# ET-FLASHEEPROM.net
KiCad netlist of a schematic drawn in Altium Designer
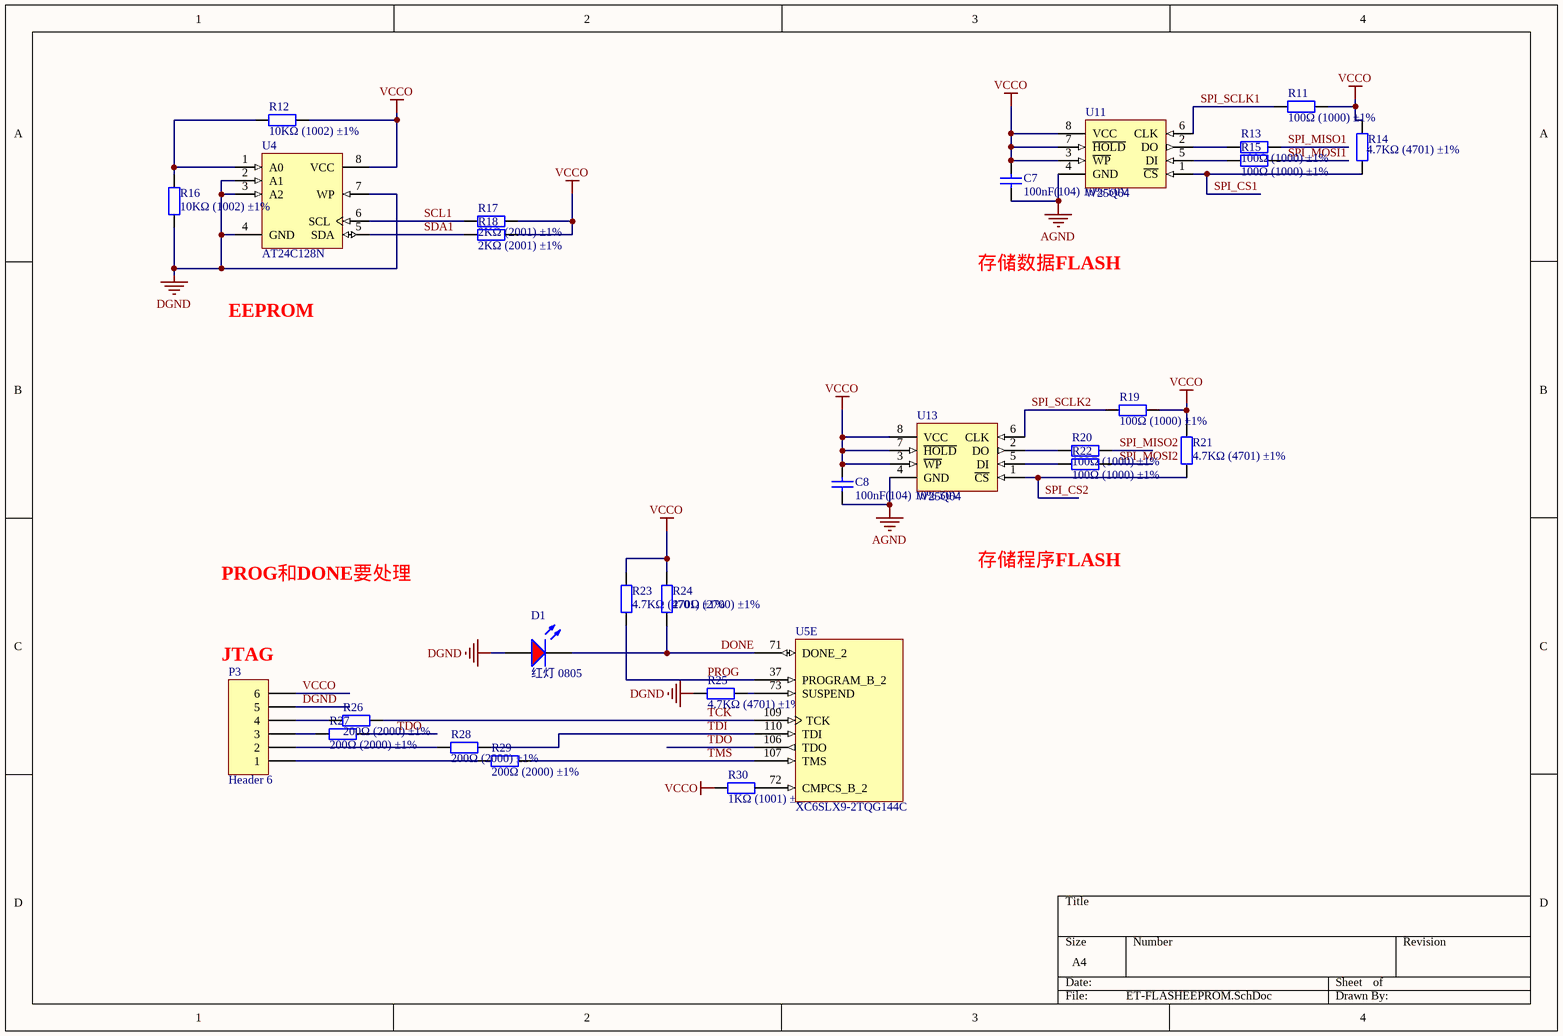
[diagram p0: ET-FLASHEEPROM.SchDoc]

(export (version "E")
  (design (tool "Eeschema 10.0.6"))
  (components
    (comp (ref "C7")
      (value "100nF(104) 10% 50V")
      (footprint "LC-0805_C")
      (description "贴片电容")
      (libsource (lib "Miscellaneous Devices LC") (part "0805 100nF(104) 10% 50V"))
    )
    (comp (ref "C8")
      (value "100nF(104) 10% 50V")
      (footprint "LC-0805_C")
      (description "贴片电容")
      (libsource (lib "Miscellaneous Devices LC") (part "0805 100nF(104) 10% 50V"))
    )
    (comp (ref "D1")
      (value "红灯 0805")
      (footprint "LC-0805_LED_S1")
      (description "发光二极管")
      (libsource (lib "Miscellaneous Devices LC") (part "0805 红灯"))
    )
    (comp (ref "P3")
      (value "Header 6")
      (footprint "HDR1X6")
      (description "Header, 6-Pin")
      (fields (field (name "PUBLISHER") "Altium Limited"))
      (libsource (lib "Miscellaneous Connectors") (part "Header 6"))
    )
    (comp (ref "R11")
      (value "100Ω (1000) ±1%")
      (footprint "LC-0805_R")
      (description "贴片电阻")
      (libsource (lib "Miscellaneous Devices LC") (part "0805 100Ω (1000) 1%"))
    )
    (comp (ref "R12")
      (value "10KΩ (1002) ±1%")
      (footprint "LC-0805_R")
      (description "贴片电阻")
      (libsource (lib "") (part "0805 10KΩ (1002) 1%_1"))
    )
    (comp (ref "R13")
      (value "100Ω (1000) ±1%")
      (footprint "LC-0805_R")
      (description "贴片电阻")
      (libsource (lib "Miscellaneous Devices LC") (part "0805 100Ω (1000) 1%"))
    )
    (comp (ref "R14")
      (value "4.7KΩ (4701) ±1%")
      (footprint "LC-0805_R")
      (description "贴片电阻")
      (libsource (lib "Miscellaneous Devices LC") (part "0805 4.7KΩ (4701) 1%"))
    )
    (comp (ref "R15")
      (value "100Ω (1000) ±1%")
      (footprint "LC-0805_R")
      (description "贴片电阻")
      (libsource (lib "Miscellaneous Devices LC") (part "0805 100Ω (1000) 1%"))
    )
    (comp (ref "R16")
      (value "10KΩ (1002) ±1%")
      (footprint "LC-0805_R")
      (description "贴片电阻")
      (libsource (lib "Miscellaneous Devices LC") (part "0805 10KΩ (1002) 1%"))
    )
    (comp (ref "R17")
      (value "2KΩ (2001) ±1%")
      (footprint "LC-0805_R")
      (description "贴片电阻")
      (libsource (lib "Miscellaneous Devices LC") (part "0805 2KΩ (2001) 1%"))
    )
    (comp (ref "R18")
      (value "2KΩ (2001) ±1%")
      (footprint "LC-0805_R")
      (description "贴片电阻")
      (libsource (lib "Miscellaneous Devices LC") (part "0805 2KΩ (2001) 1%"))
    )
    (comp (ref "R19")
      (value "100Ω (1000) ±1%")
      (footprint "LC-0805_R")
      (description "贴片电阻")
      (libsource (lib "Miscellaneous Devices LC") (part "0805 100Ω (1000) 1%"))
    )
    (comp (ref "R20")
      (value "100Ω (1000) ±1%")
      (footprint "LC-0805_R")
      (description "贴片电阻")
      (libsource (lib "Miscellaneous Devices LC") (part "0805 100Ω (1000) 1%"))
    )
    (comp (ref "R21")
      (value "4.7KΩ (4701) ±1%")
      (footprint "LC-0805_R")
      (description "贴片电阻")
      (libsource (lib "Miscellaneous Devices LC") (part "0805 4.7KΩ (4701) 1%"))
    )
    (comp (ref "R22")
      (value "100Ω (1000) ±1%")
      (footprint "LC-0805_R")
      (description "贴片电阻")
      (libsource (lib "Miscellaneous Devices LC") (part "0805 100Ω (1000) 1%"))
    )
    (comp (ref "R23")
      (value "4.7KΩ (4701) ±1%")
      (footprint "LC-0805_R")
      (description "贴片电阻")
      (libsource (lib "Miscellaneous Devices LC") (part "0805 4.7KΩ (4701) 1%"))
    )
    (comp (ref "R24")
      (value "270Ω (2700) ±1%")
      (footprint "LC-0805_R")
      (description "贴片电阻")
      (libsource (lib "Miscellaneous Devices LC") (part "0805 270Ω (2700) 1%"))
    )
    (comp (ref "R25")
      (value "4.7KΩ (4701) ±1%")
      (footprint "LC-0805_R")
      (description "贴片电阻")
      (libsource (lib "") (part "0805 4.7KΩ (4701) 1%_1"))
    )
    (comp (ref "R26")
      (value "200Ω (2000) ±1%")
      (footprint "LC-0805_R")
      (description "贴片电阻")
      (libsource (lib "Miscellaneous Devices LC") (part "0805 200Ω (2000) 1%"))
    )
    (comp (ref "R27")
      (value "200Ω (2000) ±1%")
      (footprint "LC-0805_R")
      (description "贴片电阻")
      (libsource (lib "Miscellaneous Devices LC") (part "0805 200Ω (2000) 1%"))
    )
    (comp (ref "R28")
      (value "200Ω (2000) ±1%")
      (footprint "LC-0805_R")
      (description "贴片电阻")
      (libsource (lib "Miscellaneous Devices LC") (part "0805 200Ω (2000) 1%"))
    )
    (comp (ref "R29")
      (value "200Ω (2000) ±1%")
      (footprint "LC-0805_R")
      (description "贴片电阻")
      (libsource (lib "Miscellaneous Devices LC") (part "0805 200Ω (2000) 1%"))
    )
    (comp (ref "R30")
      (value "1KΩ (1001) ±1%")
      (footprint "LC-0805_R")
      (description "贴片电阻")
      (libsource (lib "Miscellaneous Devices LC") (part "0805 1KΩ (1001) 1%"))
    )
    (comp (ref "U4")
      (value "AT24C128N")
      (footprint "8P3")
      (description "1Kbit (128 x 8), 2-wire Bus Automotive Serial EEPROM with Write Protect, 2.5V, 8-Pin SOIC, Bulk")
      (fields (field (name "PUBLISHER") "Altium Limited"))
      (libsource (lib "Atmel Memory Serial EEPROM") (part "AT24C01BN-SP25-B"))
    )
    (comp (ref "U5")
      (value "XC6SLX9-2TQG144C")
      (footprint "TQG144_N")
      (fields (field (name "PUBLISHER") "Altium Limited"))
      (libsource (lib "Xilinx Spartan-6") (part "XC6SLX9-2TQG144C"))
    )
    (comp (ref "U11")
      (value "W25Q64")
      (footprint "LC-SOIC-8_208mil")
      (libsource (lib "My Library") (part "W25Q64"))
    )
    (comp (ref "U13")
      (value "W25Q64")
      (footprint "LC-SOIC-8_208mil")
      (libsource (lib "My Library") (part "W25Q64"))
    )
  )
  (nets
    (net (code "1") (name "/DONE") (class "Default")
      (node (ref "D1") (pin "K") (pinfunction "K_K") (pintype "passive"))
      (node (ref "R24") (pin "1") (pinfunction "1_1") (pintype "passive"))
      (node (ref "U5") (pin "71") (pinfunction "DONE_2_71") (pintype "bidirectional"))
    )
    (net (code "2") (name "/PROG") (class "Default")
      (node (ref "R23") (pin "1") (pinfunction "1_1") (pintype "passive"))
      (node (ref "U5") (pin "37") (pinfunction "PROGRAM_B_2_37") (pintype "input"))
    )
    (net (code "3") (name "/SCL1") (class "Default")
      (node (ref "R17") (pin "1") (pinfunction "1_1") (pintype "passive"))
      (node (ref "U4") (pin "6") (pinfunction "SCL_6") (pintype "input"))
    )
    (net (code "4") (name "/SDA1") (class "Default")
      (node (ref "R18") (pin "1") (pinfunction "1_1") (pintype "passive"))
      (node (ref "U4") (pin "5") (pinfunction "SDA_5") (pintype "bidirectional"))
    )
    (net (code "5") (name "/SPI_CS1") (class "Default")
      (node (ref "R14") (pin "1") (pinfunction "1_1") (pintype "passive"))
      (node (ref "U11") (pin "1") (pinfunction "~{CS}_1") (pintype "input"))
    )
    (net (code "6") (name "/SPI_CS2") (class "Default")
      (node (ref "R21") (pin "1") (pinfunction "1_1") (pintype "passive"))
      (node (ref "U13") (pin "1") (pinfunction "~{CS}_1") (pintype "input"))
    )
    (net (code "7") (name "/SPI_MISO1") (class "Default")
      (node (ref "R13") (pin "2") (pinfunction "2_2") (pintype "passive"))
    )
    (net (code "8") (name "/SPI_MISO2") (class "Default")
      (node (ref "R20") (pin "2") (pinfunction "2_2") (pintype "passive"))
    )
    (net (code "9") (name "/SPI_MOSI1") (class "Default")
      (node (ref "R15") (pin "2") (pinfunction "2_2") (pintype "passive"))
    )
    (net (code "10") (name "/SPI_MOSI2") (class "Default")
      (node (ref "R22") (pin "2") (pinfunction "2_2") (pintype "passive"))
    )
    (net (code "11") (name "/SPI_SCLK1") (class "Default")
      (node (ref "R11") (pin "1") (pinfunction "1_1") (pintype "passive"))
      (node (ref "U11") (pin "6") (pinfunction "CLK_6") (pintype "input"))
    )
    (net (code "12") (name "/SPI_SCLK2") (class "Default")
      (node (ref "R19") (pin "1") (pinfunction "1_1") (pintype "passive"))
      (node (ref "U13") (pin "6") (pinfunction "CLK_6") (pintype "input"))
    )
    (net (code "13") (name "/TCK") (class "Default")
      (node (ref "R26") (pin "2") (pinfunction "2_2") (pintype "passive"))
      (node (ref "U5") (pin "109") (pinfunction "TCK_109") (pintype "input"))
    )
    (net (code "14") (name "/TDI") (class "Default")
      (node (ref "R28") (pin "2") (pinfunction "2_2") (pintype "passive"))
      (node (ref "U5") (pin "110") (pinfunction "TDI_110") (pintype "input"))
    )
    (net (code "15") (name "/TDO") (class "Default")
      (node (ref "R27") (pin "2") (pinfunction "2_2") (pintype "passive"))
      (node (ref "U5") (pin "106") (pinfunction "TDO_106") (pintype "output"))
    )
    (net (code "16") (name "/TMS") (class "Default")
      (node (ref "R29") (pin "2") (pinfunction "2_2") (pintype "passive"))
      (node (ref "U5") (pin "107") (pinfunction "TMS_107") (pintype "input"))
    )
    (net (code "17") (name "AGND") (class "Default")
      (node (ref "C7") (pin "1") (pinfunction "1_1") (pintype "passive"))
      (node (ref "C8") (pin "1") (pinfunction "1_1") (pintype "passive"))
      (node (ref "U11") (pin "4") (pinfunction "GND_4") (pintype "power_in"))
      (node (ref "U13") (pin "4") (pinfunction "GND_4") (pintype "power_in"))
    )
    (net (code "18") (name "DGND") (class "Default")
      (node (ref "D1") (pin "A") (pinfunction "A_A") (pintype "passive"))
      (node (ref "P3") (pin "5") (pinfunction "5_5") (pintype "passive"))
      (node (ref "R16") (pin "1") (pinfunction "1_1") (pintype "passive"))
      (node (ref "R25") (pin "1") (pinfunction "1_1") (pintype "passive"))
      (node (ref "U4") (pin "2") (pinfunction "A1_2") (pintype "input"))
      (node (ref "U4") (pin "3") (pinfunction "A2_3") (pintype "input"))
      (node (ref "U4") (pin "4") (pinfunction "GND_4") (pintype "power_in"))
      (node (ref "U4") (pin "7") (pinfunction "WP_7") (pintype "input"))
    )
    (net (code "19") (name "Net-(P3-Pad1)") (class "Default")
      (node (ref "P3") (pin "1") (pinfunction "1_1") (pintype "passive"))
      (node (ref "R29") (pin "1") (pinfunction "1_1") (pintype "passive"))
    )
    (net (code "20") (name "Net-(P3-Pad2)") (class "Default")
      (node (ref "P3") (pin "2") (pinfunction "2_2") (pintype "passive"))
      (node (ref "R28") (pin "1") (pinfunction "1_1") (pintype "passive"))
    )
    (net (code "21") (name "Net-(P3-Pad3)") (class "Default")
      (node (ref "P3") (pin "3") (pinfunction "3_3") (pintype "passive"))
      (node (ref "R27") (pin "1") (pinfunction "1_1") (pintype "passive"))
    )
    (net (code "22") (name "Net-(P3-Pad4)") (class "Default")
      (node (ref "P3") (pin "4") (pinfunction "4_4") (pintype "passive"))
      (node (ref "R26") (pin "1") (pinfunction "1_1") (pintype "passive"))
    )
    (net (code "23") (name "Net-(U4-A0)") (class "Default")
      (node (ref "R12") (pin "1") (pinfunction "1_1") (pintype "passive"))
      (node (ref "R16") (pin "2") (pinfunction "2_2") (pintype "passive"))
      (node (ref "U4") (pin "1") (pinfunction "A0_1") (pintype "input"))
    )
    (net (code "24") (name "Net-(U5E-CMPCS_B_2)") (class "Default")
      (node (ref "R30") (pin "2") (pinfunction "2_2") (pintype "passive"))
      (node (ref "U5") (pin "72") (pinfunction "CMPCS_B_2_72") (pintype "input"))
    )
    (net (code "25") (name "Net-(U5E-SUSPEND)") (class "Default")
      (node (ref "R25") (pin "2") (pinfunction "2_2") (pintype "passive"))
      (node (ref "U5") (pin "73") (pinfunction "SUSPEND_73") (pintype "input"))
    )
    (net (code "26") (name "Net-(U11-DI)") (class "Default")
      (node (ref "R15") (pin "1") (pinfunction "1_1") (pintype "passive"))
      (node (ref "U11") (pin "5") (pinfunction "DI_5") (pintype "input"))
    )
    (net (code "27") (name "Net-(U11-DO)") (class "Default")
      (node (ref "R13") (pin "1") (pinfunction "1_1") (pintype "passive"))
      (node (ref "U11") (pin "2") (pinfunction "DO_2") (pintype "output"))
    )
    (net (code "28") (name "Net-(U13-DI)") (class "Default")
      (node (ref "R22") (pin "1") (pinfunction "1_1") (pintype "passive"))
      (node (ref "U13") (pin "5") (pinfunction "DI_5") (pintype "input"))
    )
    (net (code "29") (name "Net-(U13-DO)") (class "Default")
      (node (ref "R20") (pin "1") (pinfunction "1_1") (pintype "passive"))
      (node (ref "U13") (pin "2") (pinfunction "DO_2") (pintype "output"))
    )
    (net (code "30") (name "VCCO") (class "Default")
      (node (ref "C7") (pin "2") (pinfunction "2_2") (pintype "passive"))
      (node (ref "C8") (pin "2") (pinfunction "2_2") (pintype "passive"))
      (node (ref "P3") (pin "6") (pinfunction "6_6") (pintype "passive"))
      (node (ref "R11") (pin "2") (pinfunction "2_2") (pintype "passive"))
      (node (ref "R12") (pin "2") (pinfunction "2_2") (pintype "passive"))
      (node (ref "R14") (pin "2") (pinfunction "2_2") (pintype "passive"))
      (node (ref "R17") (pin "2") (pinfunction "2_2") (pintype "passive"))
      (node (ref "R18") (pin "2") (pinfunction "2_2") (pintype "passive"))
      (node (ref "R19") (pin "2") (pinfunction "2_2") (pintype "passive"))
      (node (ref "R21") (pin "2") (pinfunction "2_2") (pintype "passive"))
      (node (ref "R23") (pin "2") (pinfunction "2_2") (pintype "passive"))
      (node (ref "R24") (pin "2") (pinfunction "2_2") (pintype "passive"))
      (node (ref "R30") (pin "1") (pinfunction "1_1") (pintype "passive"))
      (node (ref "U11") (pin "3") (pinfunction "~{WP}_3") (pintype "input"))
      (node (ref "U11") (pin "7") (pinfunction "~{HOLD}_7") (pintype "input"))
      (node (ref "U11") (pin "8") (pinfunction "VCC_8") (pintype "power_in"))
      (node (ref "U13") (pin "3") (pinfunction "~{WP}_3") (pintype "input"))
      (node (ref "U13") (pin "7") (pinfunction "~{HOLD}_7") (pintype "input"))
      (node (ref "U13") (pin "8") (pinfunction "VCC_8") (pintype "power_in"))
      (node (ref "U4") (pin "8") (pinfunction "VCC_8") (pintype "power_in"))
    )
  )
)
